# CAN_XCVR_5V.net
KiCad netlist of a schematic drawn in Altium Designer
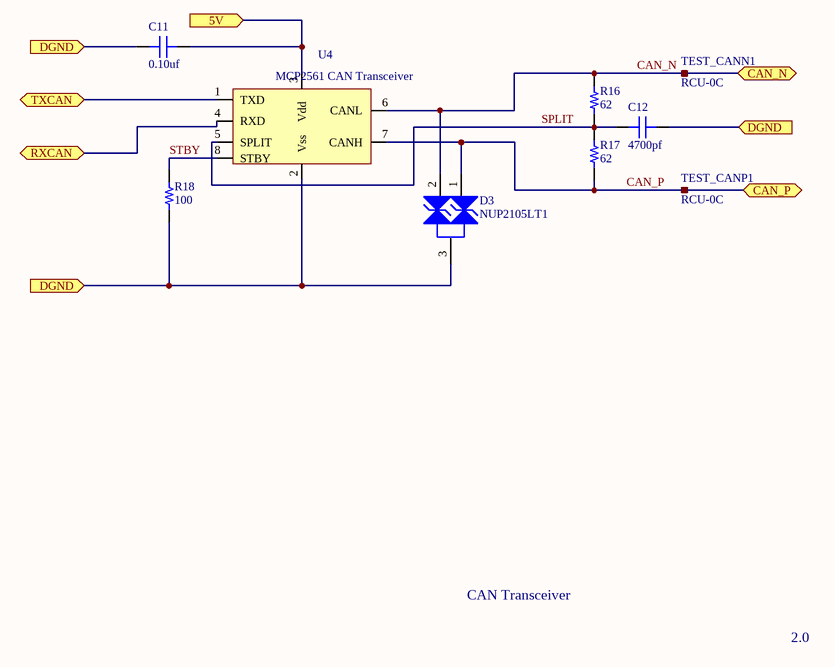
[diagram p0: CAN_XCVR_5V.SchDoc]

(export (version "E")
  (design (tool "Eeschema 10.0.6"))
  (components
    (comp (ref "C11")
      (value "0.10uf")
      (footprint "CAP 0603/1608")
      (fields
        (field (name "Comment") "Capacitor MLCC 0.10uf 50V CAP 0603/1608")
        (field (name "CREATED_BY") "Nick Mah")
      )
      (libsource (lib "Altium-Lib") (part "Capacitor"))
    )
    (comp (ref "C12")
      (value "4700pf")
      (footprint "CAP 0603/1608")
      (fields
        (field (name "Comment") "Capacitor MLCC 4700pf 50V CAP 0603/1608")
        (field (name "CREATED_BY") "Nick Mah")
      )
      (libsource (lib "Altium-Lib") (part "Capacitor"))
    )
    (comp (ref "D3")
      (value "NUP2105LT1")
      (footprint "SOT-23 (TO-236)")
      (description "ESD Protection Diode")
      (fields (field (name "POWER") "350W") (field (name "MFRPARTNO") "NUP2105LT1-ND"))
      (libsource (lib "Altium-Lib") (part "NUP2105LT1"))
    )
    (comp (ref "R16")
      (value "62")
      (footprint "RES 0603/1608")
      (fields
        (field (name "TOLERANCE") "5%")
        (field (name "POWER") "1/10W")
        (field (name "Comment") "Resistor 62 0603 1/10W 5%")
        (field (name "CREATED_BY") "Nick Mah")
      )
      (libsource (lib "Altium-Lib") (part "Resistor"))
    )
    (comp (ref "R17")
      (value "62")
      (footprint "RES 0603/1608")
      (fields
        (field (name "TOLERANCE") "5%")
        (field (name "POWER") "1/10W")
        (field (name "Comment") "Resistor 62 0603 1/10W 5%")
        (field (name "CREATED_BY") "Nick Mah")
      )
      (libsource (lib "Altium-Lib") (part "Resistor"))
    )
    (comp (ref "R18")
      (value "100")
      (footprint "RES 0603/1608")
      (fields
        (field (name "TOLERANCE") "10%")
        (field (name "POWER") "1/10W")
        (field (name "Comment") "Resistor 100 0603 1/10W 10%")
        (field (name "CREATED_BY") "Nick Mah")
      )
      (libsource (lib "Altium-Lib") (part "Resistor"))
    )
    (comp (ref "TEST_CANN1")
      (value "RCU-0C")
      (footprint "RCU-0C")
      (libsource (lib "Altium-Lib") (part "RCU-0C"))
    )
    (comp (ref "TEST_CANP1")
      (value "RCU-0C")
      (footprint "RCU-0C")
      (libsource (lib "Altium-Lib") (part "RCU-0C"))
    )
    (comp (ref "U4")
      (value "MCP2561 CAN Transceiver")
      (footprint "SOIC-8")
      (fields (field (name "MFRPARTNO") "MCP2561") (field (name "CREATED_BY") "Angel Delgado"))
      (libsource (lib "Altium-Lib") (part "MCP2561 CAN Transceiver"))
    )
  )
  (nets
    (net (code "1") (name "/5V") (class "Default")
      (node (ref "C11") (pin "2") (pinfunction "2_2") (pintype "passive"))
      (node (ref "U4") (pin "3") (pinfunction "Vdd_3") (pintype "passive"))
    )
    (net (code "2") (name "/CAN_N") (class "Default")
      (node (ref "D3") (pin "2") (pinfunction "K_2") (pintype "passive"))
      (node (ref "R16") (pin "1") (pinfunction "1_1") (pintype "passive"))
      (node (ref "TEST_CANN1") (pin "1") (pintype "passive"))
      (node (ref "U4") (pin "6") (pinfunction "CANL_6") (pintype "passive"))
    )
    (net (code "3") (name "/CAN_P") (class "Default")
      (node (ref "D3") (pin "1") (pinfunction "K_1") (pintype "passive"))
      (node (ref "R17") (pin "2") (pinfunction "2_2") (pintype "passive"))
      (node (ref "TEST_CANP1") (pin "1") (pintype "passive"))
      (node (ref "U4") (pin "7") (pinfunction "CANH_7") (pintype "passive"))
    )
    (net (code "4") (name "/DGND") (class "Default")
      (node (ref "C11") (pin "1") (pinfunction "1_1") (pintype "passive"))
      (node (ref "C12") (pin "1") (pinfunction "1_1") (pintype "passive"))
      (node (ref "D3") (pin "3") (pinfunction "K_3") (pintype "passive"))
      (node (ref "R18") (pin "1") (pinfunction "1_1") (pintype "passive"))
      (node (ref "U4") (pin "2") (pinfunction "Vss_2") (pintype "passive"))
    )
    (net (code "5") (name "/RXCAN") (class "Default")
      (node (ref "U4") (pin "4") (pinfunction "RXD_4") (pintype "passive"))
    )
    (net (code "6") (name "/SPLIT") (class "Default")
      (node (ref "C12") (pin "2") (pinfunction "2_2") (pintype "passive"))
      (node (ref "R16") (pin "2") (pinfunction "2_2") (pintype "passive"))
      (node (ref "R17") (pin "1") (pinfunction "1_1") (pintype "passive"))
      (node (ref "U4") (pin "5") (pinfunction "SPLIT_5") (pintype "passive"))
    )
    (net (code "7") (name "/STBY") (class "Default")
      (node (ref "R18") (pin "2") (pinfunction "2_2") (pintype "passive"))
      (node (ref "U4") (pin "8") (pinfunction "STBY_8") (pintype "passive"))
    )
    (net (code "8") (name "/TXCAN") (class "Default")
      (node (ref "U4") (pin "1") (pinfunction "TXD_1") (pintype "passive"))
    )
  )
)
